# ReboostV2_toplevel.net
KiCad netlist of a schematic drawn in Altium Designer
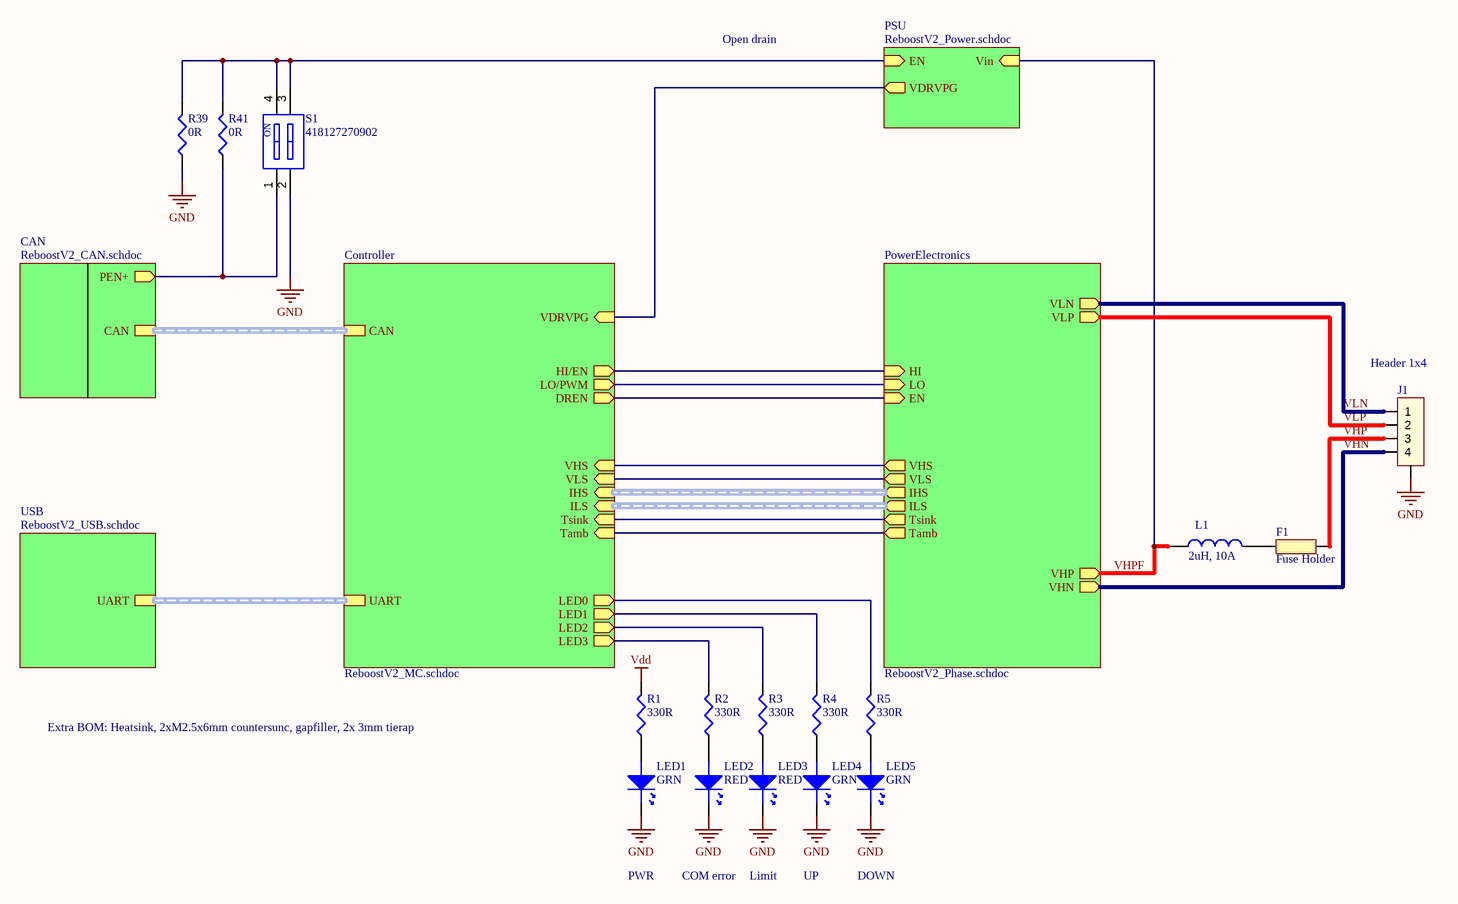
[diagram p0: ReboostV2_toplevel.SchDoc]

(export (version "E")
  (design (tool "Eeschema 10.0.6"))
  (components
    (comp (ref "F1")
      (value "Fuse Holder")
      (footprint "Fuse5x20TH")
      (description "Fuse, Holder, 10A, 250V, T:-40°C +85°C")
      (libsource (lib "AR_Misc") (part "0031.8201"))
    )
    (comp (ref "J1")
      (value "Header 1x4")
      (footprint "PC 4/ 4-G-7,62")
      (description "Header, Close Horizontal, 1x4, Male, 7.62mm, TH")
      (libsource (lib "AR_Connectors") (part "PC 4/4-G-7,62_1"))
    )
    (comp (ref "L1")
      (value "2uH, 10A")
      (footprint "744710210")
      (description "WE-SD Rod Core Choke, 2uH, 10A")
      (fields
        (field (name "MANUFACTURER PART NUMBER") "744710210")
        (field (name "MANUFACTURER") "Wurth Elektronik")
      )
      (libsource (lib "WE-SD (rev20a)") (part "744710210"))
    )
    (comp (ref "LED1")
      (value "GRN")
      (footprint "WL-SMRW_1206 cylindrical_Reverse use")
      (description "LED, Reverse Mount, Cylindrical, Green")
      (libsource (lib "AR_LEDs") (part "156120GS75300"))
    )
    (comp (ref "LED2")
      (value "RED")
      (footprint "WL-SMRW_1206 cylindrical_Reverse use")
      (description "LED, Reverse Mount, Cylindrical, Red")
      (libsource (lib "AR_LEDs") (part "156120RS75300"))
    )
    (comp (ref "LED3")
      (value "RED")
      (footprint "WL-SMRW_1206 cylindrical_Reverse use")
      (description "LED, Reverse Mount, Cylindrical, Red")
      (libsource (lib "AR_LEDs") (part "156120RS75300"))
    )
    (comp (ref "LED4")
      (value "GRN")
      (footprint "WL-SMRW_1206 cylindrical_Reverse use")
      (description "LED, Reverse Mount, Cylindrical, Green")
      (libsource (lib "AR_LEDs") (part "156120GS75300"))
    )
    (comp (ref "LED5")
      (value "GRN")
      (footprint "WL-SMRW_1206 cylindrical_Reverse use")
      (description "LED, Reverse Mount, Cylindrical, Green")
      (libsource (lib "AR_LEDs") (part "156120GS75300"))
    )
    (comp (ref "R1")
      (value "330R")
      (footprint "0603")
      (description "Resistor, 330R, 1%, 0.063W, 50V, 100PPM, 0603")
      (libsource (lib "AR_Resistors_SMD") (part "330/0603/0063W/50V"))
    )
    (comp (ref "R2")
      (value "330R")
      (footprint "0603")
      (description "Resistor, 330R, 1%, 0.063W, 50V, 100PPM, 0603")
      (libsource (lib "AR_Resistors_SMD") (part "330/0603/0063W/50V"))
    )
    (comp (ref "R3")
      (value "330R")
      (footprint "0603")
      (description "Resistor, 330R, 1%, 0.063W, 50V, 100PPM, 0603")
      (libsource (lib "AR_Resistors_SMD") (part "330/0603/0063W/50V"))
    )
    (comp (ref "R4")
      (value "330R")
      (footprint "0603")
      (description "Resistor, 330R, 1%, 0.063W, 50V, 100PPM, 0603")
      (libsource (lib "AR_Resistors_SMD") (part "330/0603/0063W/50V"))
    )
    (comp (ref "R5")
      (value "330R")
      (footprint "0603")
      (description "Resistor, 330R, 1%, 0.063W, 50V, 100PPM, 0603")
      (libsource (lib "AR_Resistors_SMD") (part "330/0603/0063W/50V"))
    )
    (comp (ref "R39")
      (value "0R")
      (footprint "0603")
      (description "Resistor, 0R, 0.1%, 0.063W, 50V, 200PPM, 0603")
      (libsource (lib "AR_Resistors_SMD") (part "0/0603/0063W/50V"))
    )
    (comp (ref "R41")
      (value "0R")
      (footprint "0603")
      (description "Resistor, 0R, 0.1%, 0.063W, 50V, 200PPM, 0603")
      (libsource (lib "AR_Resistors_SMD") (part "0/0603/0063W/50V"))
    )
    (comp (ref "S1")
      (value "418127270902")
      (footprint "418127270902")
      (description "WS-DITV Small Compact THT Dip Switch, Raised Actuator, pitch 2.54mm, 2p")
      (fields (field (name "PUBLISHER") "Wurth Elektronik"))
      (libsource (lib "Altium_WS-DITV (rev19a)") (part "418127270902"))
    )
  )
  (nets
    (net (code "3") (name "/EN") (class "Default")
      (node (ref "R39") (pin "2") (pinfunction "2_2") (pintype "passive"))
      (node (ref "R41") (pin "2") (pinfunction "2_2") (pintype "passive"))
      (node (ref "S1") (pin "3") (pinfunction "3_3") (pintype "passive"))
      (node (ref "S1") (pin "4") (pinfunction "4_4") (pintype "passive"))
    )
    (net (code "7") (name "/LED0") (class "Default")
      (node (ref "R5") (pin "2") (pinfunction "2_2") (pintype "passive"))
    )
    (net (code "8") (name "/LED1") (class "Default")
      (node (ref "R4") (pin "2") (pinfunction "2_2") (pintype "passive"))
    )
    (net (code "9") (name "/LED2") (class "Default")
      (node (ref "R3") (pin "2") (pinfunction "2_2") (pintype "passive"))
    )
    (net (code "10") (name "/LED3") (class "Default")
      (node (ref "R2") (pin "2") (pinfunction "2_2") (pintype "passive"))
    )
    (net (code "12") (name "/PEN+") (class "Default")
      (node (ref "R41") (pin "1") (pinfunction "1_1") (pintype "passive"))
      (node (ref "S1") (pin "1") (pinfunction "1_1") (pintype "passive"))
    )
    (net (code "17") (name "/VHN") (class "Default")
      (node (ref "J1") (pin "4") (pinfunction "4_4") (pintype "passive"))
    )
    (net (code "18") (name "/VHP") (class "Default")
      (node (ref "F1") (pin "2") (pinfunction "2_2") (pintype "passive"))
      (node (ref "J1") (pin "3") (pinfunction "3_3") (pintype "passive"))
    )
    (net (code "19") (name "/VHPF") (class "Default")
      (node (ref "L1") (pin "1") (pinfunction "1_1") (pintype "passive"))
    )
    (net (code "21") (name "/VLN") (class "Default")
      (node (ref "J1") (pin "1") (pinfunction "1_1") (pintype "passive"))
    )
    (net (code "22") (name "/VLP") (class "Default")
      (node (ref "J1") (pin "2") (pinfunction "2_2") (pintype "passive"))
    )
    (net (code "24") (name "GND") (class "Default")
      (node (ref "J1") (pin "0") (pinfunction "0_0") (pintype "passive"))
      (node (ref "LED1") (pin "1") (pinfunction "K_1") (pintype "passive"))
      (node (ref "LED2") (pin "1") (pinfunction "K_1") (pintype "passive"))
      (node (ref "LED3") (pin "1") (pinfunction "K_1") (pintype "passive"))
      (node (ref "LED4") (pin "1") (pinfunction "K_1") (pintype "passive"))
      (node (ref "LED5") (pin "1") (pinfunction "K_1") (pintype "passive"))
      (node (ref "R39") (pin "1") (pinfunction "1_1") (pintype "passive"))
      (node (ref "S1") (pin "2") (pinfunction "2_2") (pintype "passive"))
    )
    (net (code "25") (name "Net-(F1-Pad1)") (class "Default")
      (node (ref "F1") (pin "1") (pinfunction "1_1") (pintype "passive"))
      (node (ref "L1") (pin "2") (pinfunction "2_2") (pintype "passive"))
    )
    (net (code "26") (name "Net-(LED1-A)") (class "Default")
      (node (ref "LED1") (pin "2") (pinfunction "A_2") (pintype "passive"))
      (node (ref "R1") (pin "1") (pinfunction "1_1") (pintype "passive"))
    )
    (net (code "27") (name "Net-(LED2-A)") (class "Default")
      (node (ref "LED2") (pin "2") (pinfunction "A_2") (pintype "passive"))
      (node (ref "R2") (pin "1") (pinfunction "1_1") (pintype "passive"))
    )
    (net (code "28") (name "Net-(LED3-A)") (class "Default")
      (node (ref "LED3") (pin "2") (pinfunction "A_2") (pintype "passive"))
      (node (ref "R3") (pin "1") (pinfunction "1_1") (pintype "passive"))
    )
    (net (code "29") (name "Net-(LED4-A)") (class "Default")
      (node (ref "LED4") (pin "2") (pinfunction "A_2") (pintype "passive"))
      (node (ref "R4") (pin "1") (pinfunction "1_1") (pintype "passive"))
    )
    (net (code "30") (name "Net-(LED5-A)") (class "Default")
      (node (ref "LED5") (pin "2") (pinfunction "A_2") (pintype "passive"))
      (node (ref "R5") (pin "1") (pinfunction "1_1") (pintype "passive"))
    )
    (net (code "31") (name "Vdd") (class "Default")
      (node (ref "R1") (pin "2") (pinfunction "2_2") (pintype "passive"))
    )
  )
)
